# 02_Top_Level.net
KiCad netlist of a schematic drawn in Altium Designer
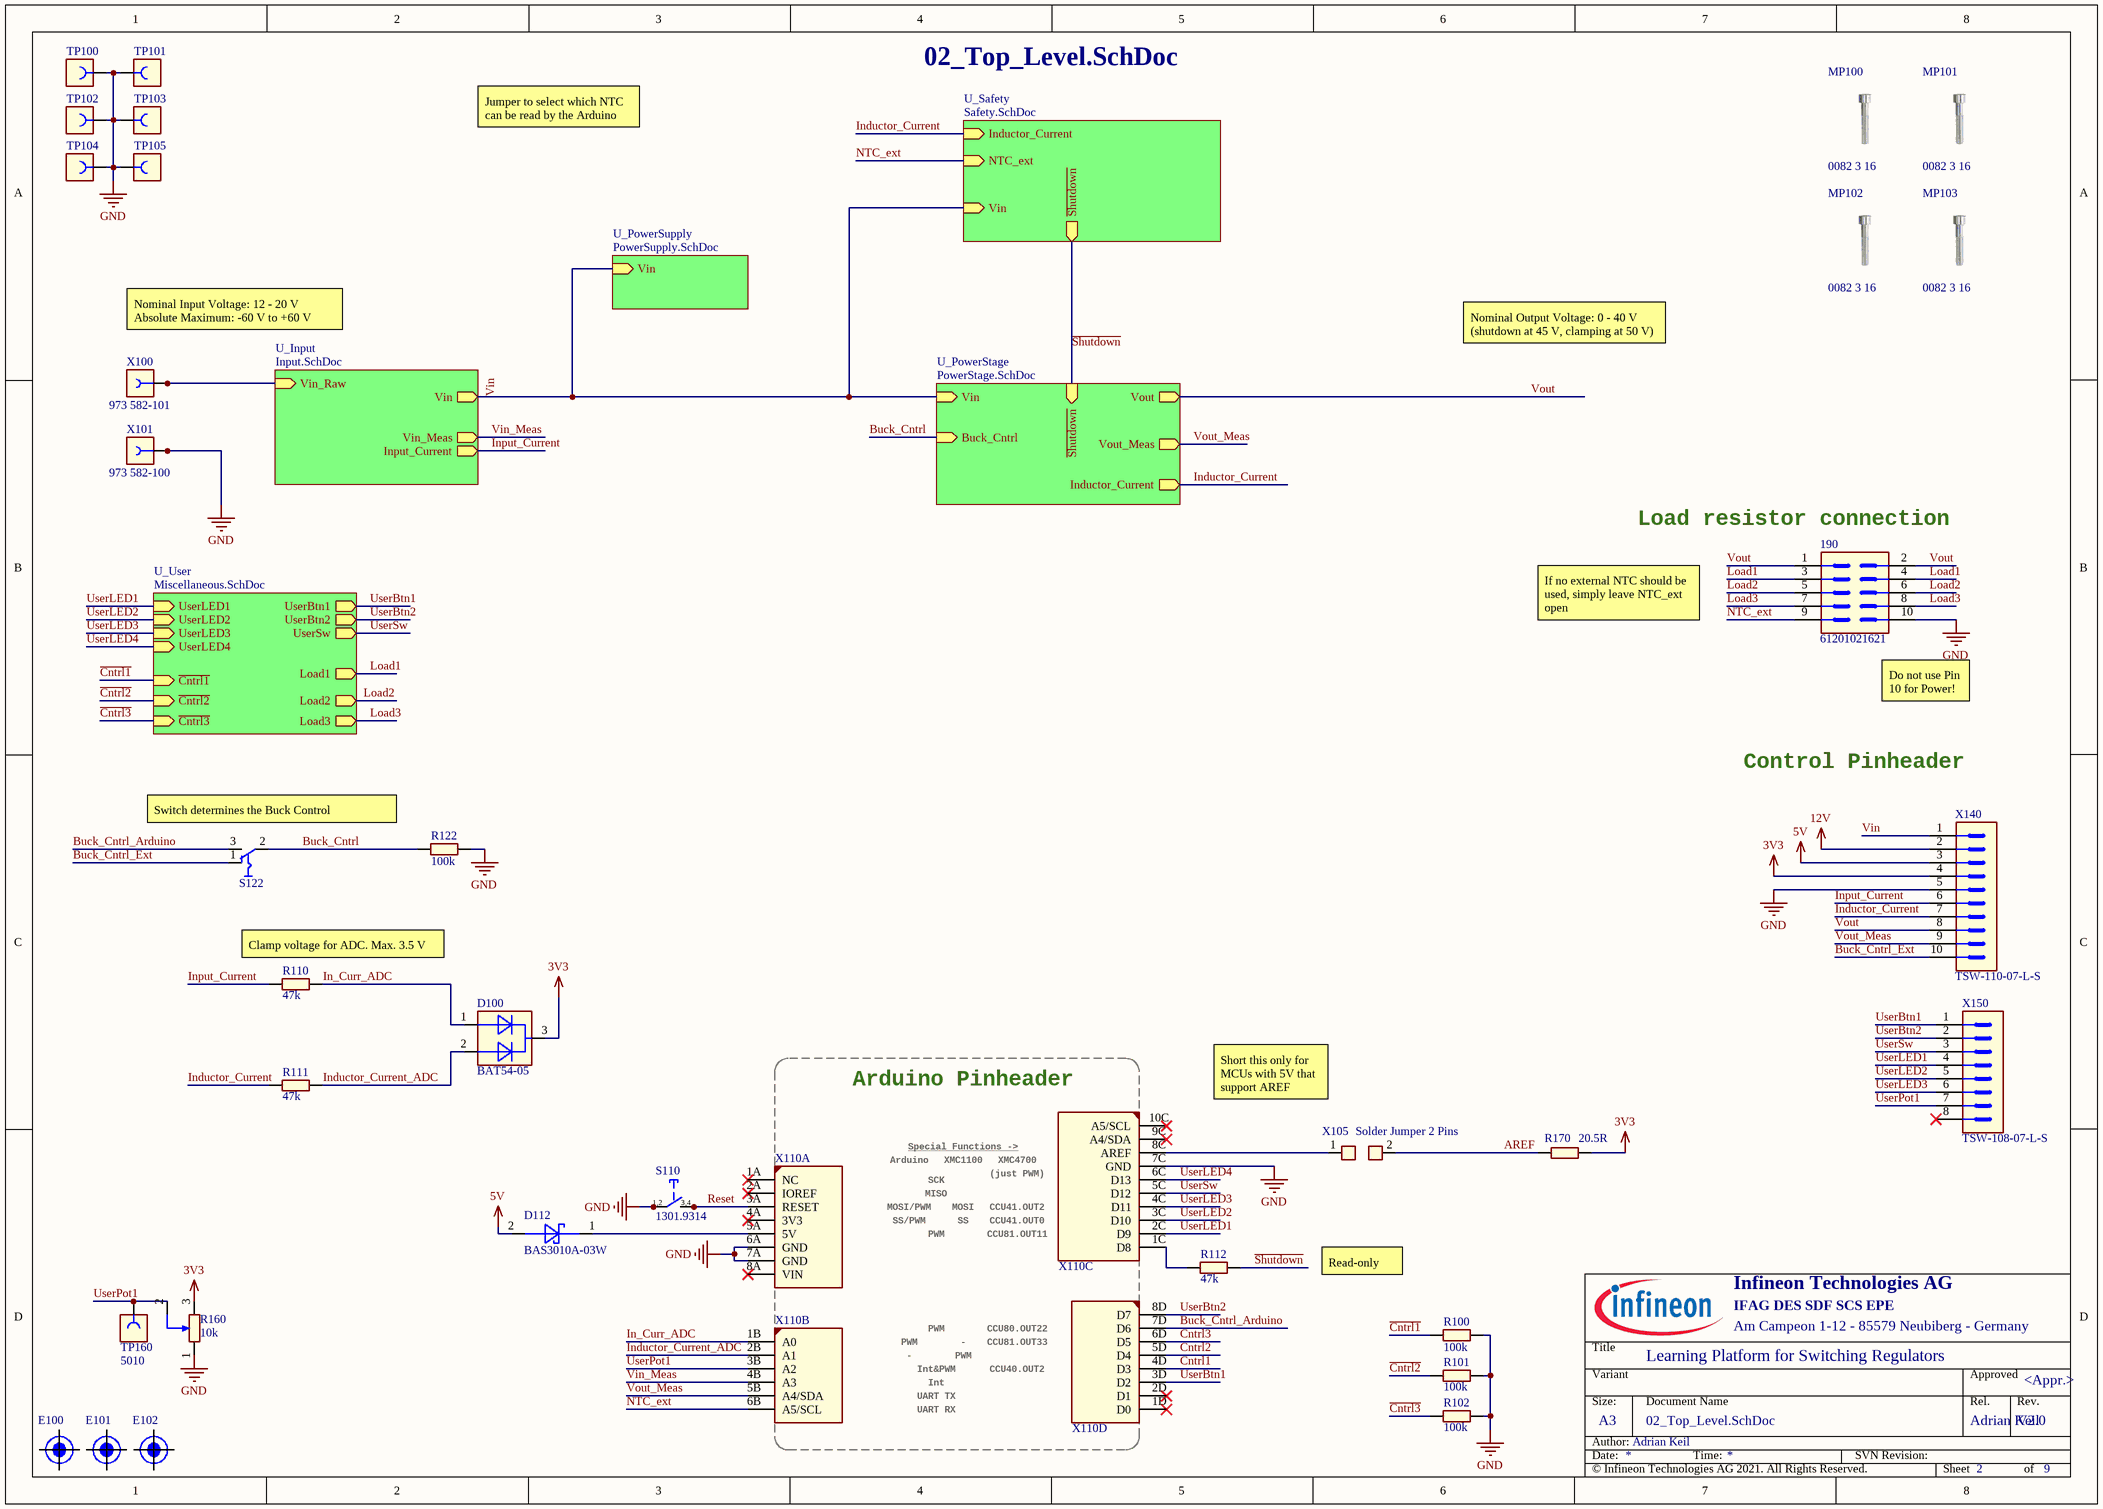
[diagram p0: 02_Top_Level.SchDoc]

(export (version "E")
  (design (tool "Eeschema 10.0.6"))
  (components
    (comp (ref "190")
      (value "61201021621")
      (footprint "CON-M-THT-61201021621")
      (description "WR-BHD Male Box Header, 2.54mm pitch, 10 pin, Vertical, Double row")
      (fields (field (name "MANUFACTURER") "Wurth Elektronik"))
      (libsource (lib "PCBLibraryData") (part "Header 5X2"))
    )
    (comp (ref "D100")
      (value "BAT54-05")
      (footprint "SOT95P240X110-3N-1-V")
      (description "Silicon Schottky Diode, LS(nH) 1.8, VR 30V")
      (fields
        (field (name "LEGACY PARTNUMBER") "IFX01401370")
        (field (name "MANUFACTURER") "Infineon Technologies")
      )
      (libsource (lib "PCBLibraryData") (part "d_dual_a1a2c3_3p"))
    )
    (comp (ref "D112")
      (value "BAS3010A-03W")
      (footprint "SOD2513X110N")
      (description "Medium Power AF Schottky Diode")
      (fields
        (field (name "LEGACY PARTNUMBER") "IFX01400145")
        (field (name "MANUFACTURER") "Infineon Technologies")
      )
      (libsource (lib "PCBLibraryData") (part "d_schottky_a"))
    )
    (comp (ref "E100")
      (value "~")
      (footprint "fiducial")
      (description "Fiducial Mark")
      (fields
        (field (name "LEGACY PARTNUMBER") "MEC10000008")
        (field (name "MANUFACTURER") "Infineon Technologies")
      )
      (libsource (lib "PCBLibraryData") (part "fiducial"))
    )
    (comp (ref "E101")
      (value "~")
      (footprint "fiducial")
      (description "Fiducial Mark")
      (fields
        (field (name "LEGACY PARTNUMBER") "MEC10000008")
        (field (name "MANUFACTURER") "Infineon Technologies")
      )
      (libsource (lib "PCBLibraryData") (part "fiducial"))
    )
    (comp (ref "E102")
      (value "~")
      (footprint "fiducial")
      (description "Fiducial Mark")
      (fields
        (field (name "LEGACY PARTNUMBER") "MEC10000008")
        (field (name "MANUFACTURER") "Infineon Technologies")
      )
      (libsource (lib "PCBLibraryData") (part "fiducial"))
    )
    (comp (ref "MP100")
      (value "0082 3 16")
      (footprint "SCREW_0082 3 16_NPTH")
      (description "Cheese Head Screw With Hexagon Socket, DIN 912 (ISO 4762), M3, 16mm length")
      (fields
        (field (name "LEGACY PARTNUMBER") "MEC10000167")
        (field (name "MANUFACTURER") "Wurth Elektronik")
      )
      (libsource (lib "PCBLibraryData") (part "Screw_0082 3 16"))
    )
    (comp (ref "MP101")
      (value "0082 3 16")
      (footprint "SCREW_0082 3 16_NPTH")
      (description "Cheese Head Screw With Hexagon Socket, DIN 912 (ISO 4762), M3, 16mm length")
      (fields
        (field (name "LEGACY PARTNUMBER") "MEC10000167")
        (field (name "MANUFACTURER") "Wurth Elektronik")
      )
      (libsource (lib "PCBLibraryData") (part "Screw_0082 3 16"))
    )
    (comp (ref "MP102")
      (value "0082 3 16")
      (footprint "SCREW_0082 3 16_NPTH")
      (description "Cheese Head Screw With Hexagon Socket, DIN 912 (ISO 4762), M3, 16mm length")
      (fields
        (field (name "LEGACY PARTNUMBER") "MEC10000167")
        (field (name "MANUFACTURER") "Wurth Elektronik")
      )
      (libsource (lib "PCBLibraryData") (part "Screw_0082 3 16"))
    )
    (comp (ref "MP103")
      (value "0082 3 16")
      (footprint "SCREW_0082 3 16_NPTH")
      (description "Cheese Head Screw With Hexagon Socket, DIN 912 (ISO 4762), M3, 16mm length")
      (fields
        (field (name "LEGACY PARTNUMBER") "MEC10000167")
        (field (name "MANUFACTURER") "Wurth Elektronik")
      )
      (libsource (lib "PCBLibraryData") (part "Screw_0082 3 16"))
    )
    (comp (ref "R100")
      (value "100k")
      (footprint "RESC3216X60N")
      (description "RES / STD / 100k / 250mW / 1% / 100ppm/K / -55°C to 155°C / 1206(3216) / SMD / -")
      (fields (field (name "LEGACY PARTNUMBER") "RES01802971") (field (name "MANUFACTURER") "Vishay"))
      (libsource (lib "PCBLibraryData") (part "RES-SGL-STD-02P_00000006"))
    )
    (comp (ref "R101")
      (value "100k")
      (footprint "RESC3216X60N")
      (description "RES / STD / 100k / 250mW / 1% / 100ppm/K / -55°C to 155°C / 1206(3216) / SMD / -")
      (fields (field (name "LEGACY PARTNUMBER") "RES01802971") (field (name "MANUFACTURER") "Vishay"))
      (libsource (lib "PCBLibraryData") (part "RES-SGL-STD-02P_00000006"))
    )
    (comp (ref "R102")
      (value "100k")
      (footprint "RESC3216X60N")
      (description "RES / STD / 100k / 250mW / 1% / 100ppm/K / -55°C to 155°C / 1206(3216) / SMD / -")
      (fields (field (name "LEGACY PARTNUMBER") "RES01802971") (field (name "MANUFACTURER") "Vishay"))
      (libsource (lib "PCBLibraryData") (part "RES-SGL-STD-02P_00000006"))
    )
    (comp (ref "R110")
      (value "47k")
      (footprint "RESC3216X60N")
      (description "RES / STD / 47k / 250mW / 1% / 100ppm/K / -55°C to 155°C / 1206(3216) / SMD / -")
      (fields (field (name "LEGACY PARTNUMBER") "RES01802933") (field (name "MANUFACTURER") "Vishay"))
      (libsource (lib "") (part "RES-SGL-STD-02P_00000006_1"))
    )
    (comp (ref "R111")
      (value "47k")
      (footprint "RESC3216X60N")
      (description "RES / STD / 47k / 250mW / 1% / 100ppm/K / -55°C to 155°C / 1206(3216) / SMD / -")
      (fields (field (name "LEGACY PARTNUMBER") "RES01802933") (field (name "MANUFACTURER") "Vishay"))
      (libsource (lib "") (part "RES-SGL-STD-02P_00000006_1"))
    )
    (comp (ref "R112")
      (value "47k")
      (footprint "RESC3216X60N")
      (description "RES / STD / 47k / 250mW / 1% / 100ppm/K / -55°C to 155°C / 1206(3216) / SMD / -")
      (fields (field (name "LEGACY PARTNUMBER") "RES01802933") (field (name "MANUFACTURER") "Vishay"))
      (libsource (lib "") (part "RES-SGL-STD-02P_00000006_1"))
    )
    (comp (ref "R122")
      (value "100k")
      (footprint "RESC3216X60N")
      (description "RES / STD / 100k / 250mW / 1% / 100ppm/K / -55°C to 155°C / 1206(3216) / SMD / -")
      (fields (field (name "LEGACY PARTNUMBER") "RES01802971") (field (name "MANUFACTURER") "Vishay"))
      (libsource (lib "PCBLibraryData") (part "RES-SGL-STD-02P_00000006"))
    )
    (comp (ref "R160")
      (value "10k")
      (footprint "POT-THT-3362P")
      (fields (field (name "MANUFACTURER") "Bourns"))
      (libsource (lib "PCBLibraryData") (part "RES-SGL-VAR-03P_00000026"))
    )
    (comp (ref "R170")
      (value "20.5R")
      (footprint "RESC3216X60N")
      (description "RES / STD / 20.5R / 250mW / 1% / 100ppm/K / -55°C to 155°C / 1206(3216) / SMD / -")
      (fields (field (name "LEGACY PARTNUMBER") "RES01802548") (field (name "MANUFACTURER") "Vishay"))
      (libsource (lib "PCBLibraryData") (part "RES-SGL-STD-02P_00000006"))
    )
    (comp (ref "S110")
      (value "1301.9314")
      (footprint "SW-SMD-1301.9314")
      (description "Pushbutton Tactile Switch, Single Pole Single Throw, 4 Pins")
      (fields (field (name "LEGACY PARTNUMBER") "CON01500305") (field (name "MANUFACTURER") "Schurter"))
      (libsource (lib "PCBLibraryData") (part "sw_sr_no12_34_4p"))
    )
    (comp (ref "S122")
      (value "CL-SB-12A-01T")
      (footprint "SW-SMD-CL-SB-12A-01T")
      (description "Slid Switch, 12V, 200mA")
      (fields (field (name "MANUFACTURER") "NIDEC COPAL ELECTRONICS, Inc."))
      (libsource (lib "PCBLibraryData") (part "sw_co213_3p"))
    )
    (comp (ref "TP100")
      (value "5011")
      (footprint "CON-THT-TP-5011")
      (description "PC Test Point-Multipurpose THT, Black")
      (fields
        (field (name "LEGACY PARTNUMBER") "CON01500530")
        (field (name "MANUFACTURER") "Keystone Electronics Corp.")
      )
      (libsource (lib "") (part "connector_1_f_1"))
    )
    (comp (ref "TP101")
      (value "5011")
      (footprint "CON-THT-TP-5011")
      (description "PC Test Point-Multipurpose THT, Black")
      (fields
        (field (name "LEGACY PARTNUMBER") "CON01500530")
        (field (name "MANUFACTURER") "Keystone Electronics Corp.")
      )
      (libsource (lib "PCBLibraryData") (part "connector_1_f"))
    )
    (comp (ref "TP102")
      (value "5011")
      (footprint "CON-THT-TP-5011")
      (description "PC Test Point-Multipurpose THT, Black")
      (fields
        (field (name "LEGACY PARTNUMBER") "CON01500530")
        (field (name "MANUFACTURER") "Keystone Electronics Corp.")
      )
      (libsource (lib "") (part "connector_1_f_1"))
    )
    (comp (ref "TP103")
      (value "5011")
      (footprint "CON-THT-TP-5011")
      (description "PC Test Point-Multipurpose THT, Black")
      (fields
        (field (name "LEGACY PARTNUMBER") "CON01500530")
        (field (name "MANUFACTURER") "Keystone Electronics Corp.")
      )
      (libsource (lib "PCBLibraryData") (part "connector_1_f"))
    )
    (comp (ref "TP104")
      (value "5011")
      (footprint "CON-THT-TP-5011")
      (description "PC Test Point-Multipurpose THT, Black")
      (fields
        (field (name "LEGACY PARTNUMBER") "CON01500530")
        (field (name "MANUFACTURER") "Keystone Electronics Corp.")
      )
      (libsource (lib "") (part "connector_1_f_1"))
    )
    (comp (ref "TP105")
      (value "5011")
      (footprint "CON-THT-TP-5011")
      (description "PC Test Point-Multipurpose THT, Black")
      (fields
        (field (name "LEGACY PARTNUMBER") "CON01500530")
        (field (name "MANUFACTURER") "Keystone Electronics Corp.")
      )
      (libsource (lib "PCBLibraryData") (part "connector_1_f"))
    )
    (comp (ref "TP160")
      (value "5010")
      (footprint "CON-THT-TP-5010")
      (description "PC Test Point-Multipurpose THT, Red")
      (fields
        (field (name "LEGACY PARTNUMBER") "CON01500529")
        (field (name "MANUFACTURER") "Keystone Electronics Corp.")
      )
      (libsource (lib "") (part "connector_1_f_2"))
    )
    (comp (ref "X100")
      (value "973 582-101")
      (footprint "CON-THT-973 582- 101")
      (description "Banana Socket, Red, 17.5mm Pitch")
      (fields
        (field (name "LEGACY PARTNUMBER") "CON01500041")
        (field (name "MANUFACTURER") "Hirschmann Test & Measurement")
      )
      (libsource (lib "PCBLibraryData") (part "soc_banana_2p"))
    )
    (comp (ref "X101")
      (value "973 582-100")
      (footprint "CON-THT-973 582- 100")
      (description "Banana Socket, black, 17.5mm Pitch")
      (fields
        (field (name "LEGACY PARTNUMBER") "CON01500045")
        (field (name "MANUFACTURER") "Hirschmann Test & Measurement")
      )
      (libsource (lib "PCBLibraryData") (part "soc_banana_2p"))
    )
    (comp (ref "X105")
      (value "Solder Jumper 2 Pins")
      (footprint "SOLDER_BRIDGE_0.7X1.299PAD")
      (fields
        (field (name "LEGACY PARTNUMBER") "CON01500959")
        (field (name "MANUFACTURER") "Infineon Technologies")
      )
      (libsource (lib "PCBLibraryData") (part "SJP_2P"))
    )
    (comp (ref "X110")
      (value "Arduino-Uno")
      (footprint "Arduino-Uno")
      (description "Arduino Uno is a microcontroller board based on the ATmega328P")
      (fields (field (name "MANUFACTURER") "Infineon Technologies"))
      (libsource (lib "PCBLibraryData") (part "Arduino-Uno"))
    )
    (comp (ref "X140")
      (value "TSW-110-07-L-S")
      (footprint "CON-M-THT-TSW-110-07-L-S")
      (description "Through hole .025 SQ Post Header, 2.54mm pitch, 10 pin, vertical, single row")
      (fields (field (name "LEGACY PARTNUMBER") "CON01500578") (field (name "MANUFACTURER") "Samtec"))
      (libsource (lib "PCBLibraryData") (part "Header 10"))
    )
    (comp (ref "X150")
      (value "TSW-108-07-L-S")
      (footprint "CON-M-THT-TSW-108-07-L-S")
      (description "Through hole .025 SQ Post Header, 2.54mm pitch, 8 pin, vertical, single row")
      (fields (field (name "LEGACY PARTNUMBER") "CON01500577") (field (name "MANUFACTURER") "Samtec"))
      (libsource (lib "PCBLibraryData") (part "Header 8"))
    )
  )
  (nets
    (net (code "1") (name "/AREF") (class "Default")
      (node (ref "R170") (pin "1") (pinfunction "1_1") (pintype "passive"))
      (node (ref "X105") (pin "2") (pinfunction "2_2") (pintype "passive"))
    )
    (net (code "2") (name "/Buck_Cntrl") (class "Default")
      (node (ref "R122") (pin "1") (pinfunction "1_1") (pintype "passive"))
      (node (ref "S122") (pin "2") (pinfunction "2_2") (pintype "passive"))
    )
    (net (code "3") (name "/Buck_Cntrl_Arduino") (class "Default")
      (node (ref "S122") (pin "3") (pinfunction "3_3") (pintype "passive"))
      (node (ref "X110") (pin "7D") (pinfunction "D6_7D") (pintype "passive"))
    )
    (net (code "4") (name "/Buck_Cntrl_Ext") (class "Default")
      (node (ref "S122") (pin "1") (pinfunction "1_1") (pintype "passive"))
      (node (ref "X140") (pin "10") (pinfunction "10_10") (pintype "passive"))
    )
    (net (code "5") (name "/Cntrl1") (class "Default")
      (node (ref "R100") (pin "1") (pinfunction "1_1") (pintype "passive"))
      (node (ref "X110") (pin "4D") (pinfunction "D3_4D") (pintype "passive"))
    )
    (net (code "6") (name "/Cntrl2") (class "Default")
      (node (ref "R101") (pin "1") (pinfunction "1_1") (pintype "passive"))
      (node (ref "X110") (pin "5D") (pinfunction "D4_5D") (pintype "passive"))
    )
    (net (code "7") (name "/Cntrl3") (class "Default")
      (node (ref "R102") (pin "1") (pinfunction "1_1") (pintype "passive"))
      (node (ref "X110") (pin "6D") (pinfunction "D5_6D") (pintype "passive"))
    )
    (net (code "8") (name "/In_Curr_ADC") (class "Default")
      (node (ref "D100") (pin "1") (pinfunction "ANODE_1_1") (pintype "passive"))
      (node (ref "R110") (pin "1") (pinfunction "1_1") (pintype "passive"))
      (node (ref "X110") (pin "1B") (pinfunction "A0_1B") (pintype "passive"))
    )
    (net (code "9") (name "/Inductor_Current") (class "Default")
      (node (ref "R111") (pin "2") (pinfunction "2_2") (pintype "passive"))
      (node (ref "X140") (pin "7") (pinfunction "7_7") (pintype "passive"))
    )
    (net (code "10") (name "/Inductor_Current_ADC") (class "Default")
      (node (ref "D100") (pin "2") (pinfunction "ANODE_2_2") (pintype "passive"))
      (node (ref "R111") (pin "1") (pinfunction "1_1") (pintype "passive"))
      (node (ref "X110") (pin "2B") (pinfunction "A1_2B") (pintype "passive"))
    )
    (net (code "11") (name "/Input_Current") (class "Default")
      (node (ref "R110") (pin "2") (pinfunction "2_2") (pintype "passive"))
      (node (ref "X140") (pin "6") (pinfunction "6_6") (pintype "passive"))
    )
    (net (code "12") (name "/Load1") (class "Default")
      (node (ref "190") (pin "3") (pinfunction "3_3") (pintype "passive"))
      (node (ref "190") (pin "4") (pinfunction "4_4") (pintype "passive"))
    )
    (net (code "13") (name "/Load2") (class "Default")
      (node (ref "190") (pin "5") (pinfunction "5_5") (pintype "passive"))
      (node (ref "190") (pin "6") (pinfunction "6_6") (pintype "passive"))
    )
    (net (code "14") (name "/Load3") (class "Default")
      (node (ref "190") (pin "7") (pinfunction "7_7") (pintype "passive"))
      (node (ref "190") (pin "8") (pinfunction "8_8") (pintype "passive"))
    )
    (net (code "15") (name "/NTC_ext") (class "Default")
      (node (ref "190") (pin "9") (pinfunction "9_9") (pintype "passive"))
      (node (ref "X110") (pin "6B") (pinfunction "A5/SCL_6B") (pintype "passive"))
    )
    (net (code "16") (name "/Reset") (class "Default")
      (node (ref "S110") (pin "3") (pinfunction "3_3") (pintype "passive"))
      (node (ref "S110") (pin "4") (pinfunction "4_4") (pintype "passive"))
      (node (ref "X110") (pin "3A") (pinfunction "RESET_3A") (pintype "passive"))
    )
    (net (code "17") (name "/Shutdown") (class "Default")
      (node (ref "R112") (pin "1") (pinfunction "1_1") (pintype "passive"))
    )
    (net (code "18") (name "/UserBtn1") (class "Default")
      (node (ref "X110") (pin "3D") (pinfunction "D2_3D") (pintype "passive"))
      (node (ref "X150") (pin "1") (pinfunction "1_1") (pintype "passive"))
    )
    (net (code "19") (name "/UserBtn2") (class "Default")
      (node (ref "X110") (pin "8D") (pinfunction "D7_8D") (pintype "passive"))
      (node (ref "X150") (pin "2") (pinfunction "2_2") (pintype "passive"))
    )
    (net (code "20") (name "/UserLED1") (class "Default")
      (node (ref "X110") (pin "2C") (pinfunction "D9_2C") (pintype "passive"))
      (node (ref "X150") (pin "4") (pinfunction "4_4") (pintype "passive"))
    )
    (net (code "21") (name "/UserLED2") (class "Default")
      (node (ref "X110") (pin "3C") (pinfunction "D10_3C") (pintype "passive"))
      (node (ref "X150") (pin "5") (pinfunction "5_5") (pintype "passive"))
    )
    (net (code "22") (name "/UserLED3") (class "Default")
      (node (ref "X110") (pin "4C") (pinfunction "D11_4C") (pintype "passive"))
      (node (ref "X150") (pin "6") (pinfunction "6_6") (pintype "passive"))
    )
    (net (code "23") (name "/UserLED4") (class "Default")
      (node (ref "X110") (pin "6C") (pinfunction "D13_6C") (pintype "passive"))
    )
    (net (code "24") (name "/UserPot1") (class "Default")
      (node (ref "R160") (pin "2") (pinfunction "2_2") (pintype "passive"))
      (node (ref "TP160") (pin "1") (pinfunction "1_1") (pintype "passive"))
      (node (ref "X110") (pin "3B") (pinfunction "A2_3B") (pintype "passive"))
      (node (ref "X150") (pin "7") (pinfunction "7_7") (pintype "passive"))
    )
    (net (code "25") (name "/UserSw") (class "Default")
      (node (ref "X110") (pin "5C") (pinfunction "D12_5C") (pintype "passive"))
      (node (ref "X150") (pin "3") (pinfunction "3_3") (pintype "passive"))
    )
    (net (code "26") (name "/Vin") (class "Default")
      (node (ref "X140") (pin "1") (pinfunction "1_1") (pintype "passive"))
    )
    (net (code "27") (name "/Vin_Meas") (class "Default")
      (node (ref "X110") (pin "4B") (pinfunction "A3_4B") (pintype "passive"))
    )
    (net (code "28") (name "/Vin_Raw") (class "Default")
      (node (ref "X100") (pin "1") (pinfunction "1_1") (pintype "passive"))
      (node (ref "X100") (pin "2") (pinfunction "2_2") (pintype "passive"))
    )
    (net (code "29") (name "/Vout") (class "Default")
      (node (ref "190") (pin "1") (pinfunction "1_1") (pintype "passive"))
      (node (ref "190") (pin "2") (pinfunction "2_2") (pintype "passive"))
      (node (ref "X140") (pin "8") (pinfunction "8_8") (pintype "passive"))
    )
    (net (code "30") (name "/Vout_Meas") (class "Default")
      (node (ref "X110") (pin "5B") (pinfunction "A4/SDA_5B") (pintype "passive"))
      (node (ref "X140") (pin "9") (pinfunction "9_9") (pintype "passive"))
    )
    (net (code "31") (name "3V3") (class "Default")
      (node (ref "D100") (pin "3") (pinfunction "CATHODE_3") (pintype "passive"))
      (node (ref "R160") (pin "3") (pinfunction "3_3") (pintype "passive"))
      (node (ref "R170") (pin "2") (pinfunction "2_2") (pintype "passive"))
      (node (ref "X140") (pin "4") (pinfunction "4_4") (pintype "passive"))
    )
    (net (code "32") (name "5V") (class "Default")
      (node (ref "D112") (pin "2") (pinfunction "Anode_2") (pintype "passive"))
      (node (ref "X140") (pin "3") (pinfunction "3_3") (pintype "passive"))
    )
    (net (code "33") (name "12V") (class "Default")
      (node (ref "X140") (pin "2") (pinfunction "2_2") (pintype "passive"))
    )
    (net (code "34") (name "GND") (class "Default")
      (node (ref "190") (pin "10") (pinfunction "10_10") (pintype "passive"))
      (node (ref "R100") (pin "2") (pinfunction "2_2") (pintype "passive"))
      (node (ref "R101") (pin "2") (pinfunction "2_2") (pintype "passive"))
      (node (ref "R102") (pin "2") (pinfunction "2_2") (pintype "passive"))
      (node (ref "R122") (pin "2") (pinfunction "2_2") (pintype "passive"))
      (node (ref "R160") (pin "1") (pinfunction "1_1") (pintype "passive"))
      (node (ref "S110") (pin "1") (pinfunction "1_1") (pintype "passive"))
      (node (ref "S110") (pin "2") (pinfunction "2_2") (pintype "passive"))
      (node (ref "TP100") (pin "1") (pinfunction "1_1") (pintype "passive"))
      (node (ref "TP101") (pin "1") (pinfunction "1_1") (pintype "passive"))
      (node (ref "TP102") (pin "1") (pinfunction "1_1") (pintype "passive"))
      (node (ref "TP103") (pin "1") (pinfunction "1_1") (pintype "passive"))
      (node (ref "TP104") (pin "1") (pinfunction "1_1") (pintype "passive"))
      (node (ref "TP105") (pin "1") (pinfunction "1_1") (pintype "passive"))
      (node (ref "X101") (pin "1") (pinfunction "1_1") (pintype "passive"))
      (node (ref "X101") (pin "2") (pinfunction "2_2") (pintype "passive"))
      (node (ref "X110") (pin "6A") (pinfunction "GND_6A") (pintype "passive"))
      (node (ref "X110") (pin "7A") (pinfunction "GND_7A") (pintype "passive"))
      (node (ref "X110") (pin "7C") (pinfunction "GND_7C") (pintype "passive"))
      (node (ref "X140") (pin "5") (pinfunction "5_5") (pintype "passive"))
    )
    (net (code "35") (name "Net-(D112-Cathode)") (class "Default")
      (node (ref "D112") (pin "1") (pinfunction "Cathode_1") (pintype "passive"))
      (node (ref "X110") (pin "5A") (pinfunction "5V_5A") (pintype "passive"))
    )
    (net (code "36") (name "Net-(X110C-AREF)") (class "Default")
      (node (ref "X105") (pin "1") (pinfunction "1_1") (pintype "passive"))
      (node (ref "X110") (pin "8C") (pinfunction "AREF_8C") (pintype "passive"))
    )
    (net (code "37") (name "Net-(X110C-D8)") (class "Default")
      (node (ref "R112") (pin "2") (pinfunction "2_2") (pintype "passive"))
      (node (ref "X110") (pin "1C") (pinfunction "D8_1C") (pintype "passive"))
    )
    (net (code "38") (name "unconnected-(E100-Pad1)") (class "Default")
      (node (ref "E100") (pin "1") (pinfunction "1_1") (pintype "passive"))
    )
    (net (code "39") (name "unconnected-(E101-Pad1)") (class "Default")
      (node (ref "E101") (pin "1") (pinfunction "1_1") (pintype "passive"))
    )
    (net (code "40") (name "unconnected-(E102-Pad1)") (class "Default")
      (node (ref "E102") (pin "1") (pinfunction "1_1") (pintype "passive"))
    )
    (net (code "41") (name "unconnected-(X110A-3V3-Pad4A)") (class "Default")
      (node (ref "X110") (pin "4A") (pinfunction "3V3_4A") (pintype "passive+no_connect"))
    )
    (net (code "42") (name "unconnected-(X110A-IOREF-Pad2A)") (class "Default")
      (node (ref "X110") (pin "2A") (pinfunction "IOREF_2A") (pintype "passive+no_connect"))
    )
    (net (code "43") (name "unconnected-(X110A-NC-Pad1A)") (class "Default")
      (node (ref "X110") (pin "1A") (pinfunction "NC_1A") (pintype "passive+no_connect"))
    )
    (net (code "44") (name "unconnected-(X110A-VIN-Pad8A)") (class "Default")
      (node (ref "X110") (pin "8A") (pinfunction "VIN_8A") (pintype "passive+no_connect"))
    )
    (net (code "45") (name "unconnected-(X110C-A4{slash}SDA-Pad9C)") (class "Default")
      (node (ref "X110") (pin "9C") (pinfunction "A4/SDA_9C") (pintype "passive+no_connect"))
    )
    (net (code "46") (name "unconnected-(X110C-A5{slash}SCL-Pad10C)") (class "Default")
      (node (ref "X110") (pin "10C") (pinfunction "A5/SCL_10C") (pintype "passive+no_connect"))
    )
    (net (code "47") (name "unconnected-(X110D-D0-Pad1D)") (class "Default")
      (node (ref "X110") (pin "1D") (pinfunction "D0_1D") (pintype "passive+no_connect"))
    )
    (net (code "48") (name "unconnected-(X110D-D1-Pad2D)") (class "Default")
      (node (ref "X110") (pin "2D") (pinfunction "D1_2D") (pintype "passive+no_connect"))
    )
    (net (code "49") (name "unconnected-(X150-Pad8)") (class "Default")
      (node (ref "X150") (pin "8") (pinfunction "8_8") (pintype "passive+no_connect"))
    )
  )
)
